# ACDC_Flyback.net
KiCad netlist of a schematic drawn in Altium Designer
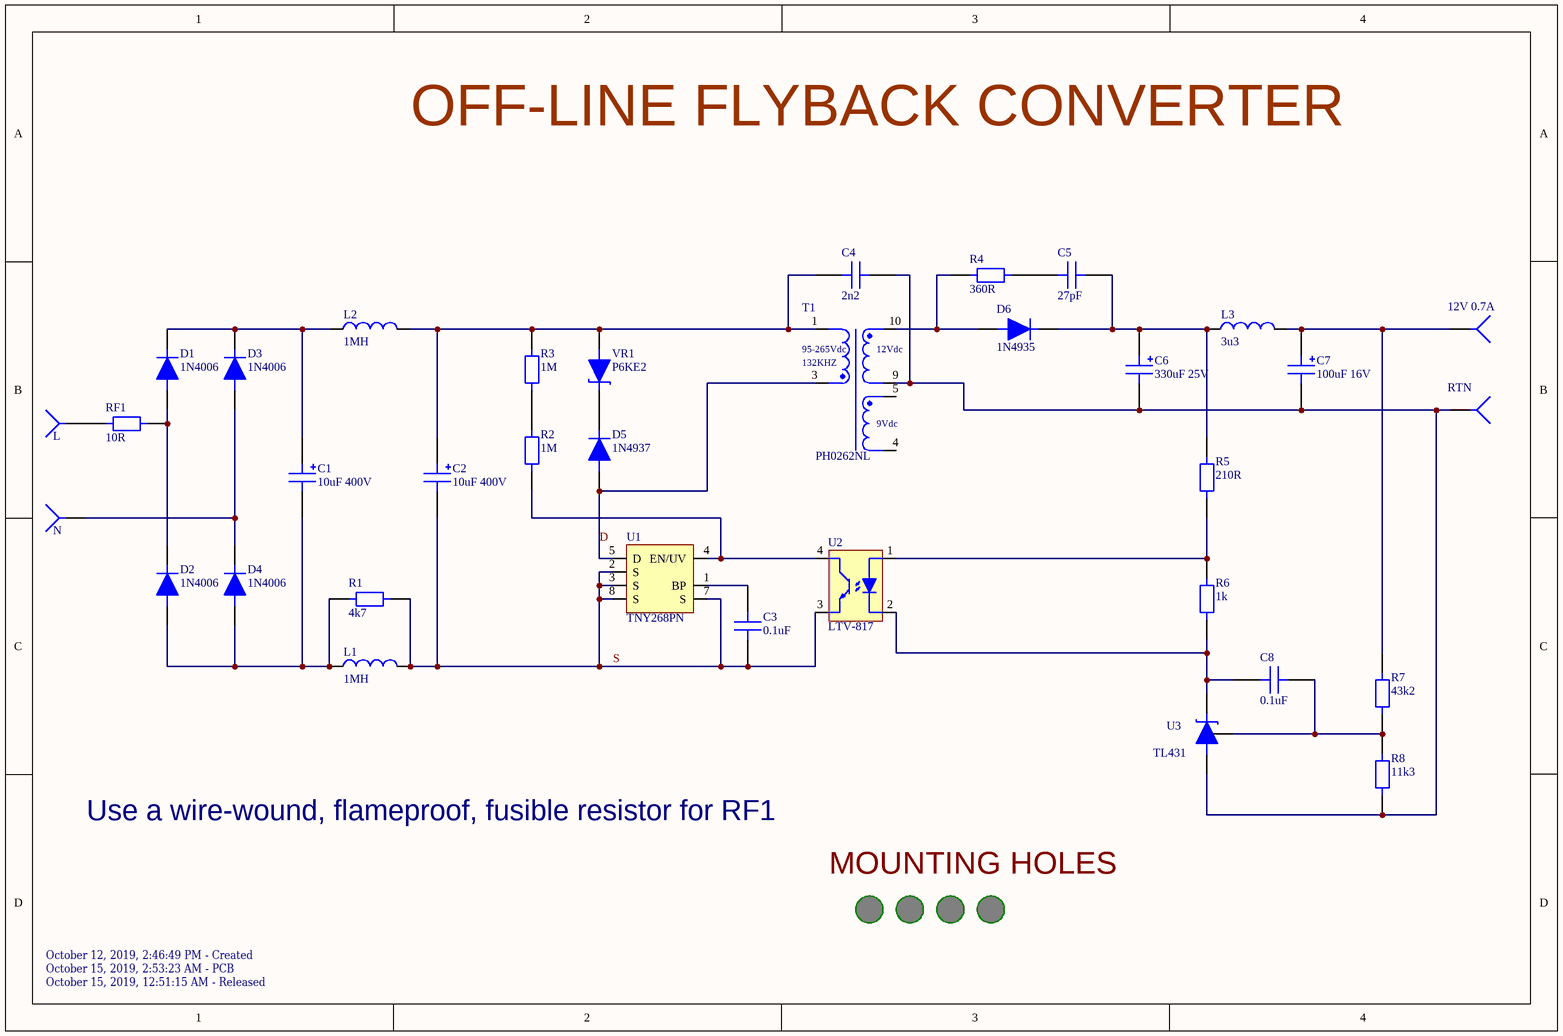
[diagram p0: ACDC_Flyback.SchDoc]

(export (version "E")
  (design (tool "Eeschema 10.0.6"))
  (components
    (comp (ref "1")
      (value "MNT HOLE 3.5mm")
      (footprint "MNT HOLE 3.5mm")
      (libsource (lib "Pwrlib") (part "MNT HOLE 3.5mm"))
    )
    (comp (ref "2")
      (value "MNT HOLE 3.5mm")
      (footprint "MNT HOLE 3.5mm")
      (libsource (lib "Pwrlib") (part "MNT HOLE 3.5mm"))
    )
    (comp (ref "3")
      (value "MNT HOLE 3.5mm")
      (footprint "MNT HOLE 3.5mm")
      (libsource (lib "Pwrlib") (part "MNT HOLE 3.5mm"))
    )
    (comp (ref "4")
      (value "MNT HOLE 3.5mm")
      (footprint "MNT HOLE 3.5mm")
      (libsource (lib "Pwrlib") (part "MNT HOLE 3.5mm"))
    )
    (comp (ref "C1")
      (value "10uF 400V")
      (footprint "CAP 10x20")
      (description "CAP ALUM 10uF 400V 10x20")
      (fields
        (field (name "MANUFACTURER") "United Chemi-Con")
        (field (name "MANUFACTURER PART NUMBER") "EKXG401ETD100MJ20S")
      )
      (libsource (lib "Pwrlib") (part "EKXG401ETD100MJ20S"))
    )
    (comp (ref "C2")
      (value "10uF 400V")
      (footprint "CAP 10x20")
      (description "CAP ALUM 10uF 400V 10x20")
      (fields
        (field (name "MANUFACTURER") "United Chemi-Con")
        (field (name "MANUFACTURER PART NUMBER") "EKXG401ETD100MJ20S")
      )
      (libsource (lib "Pwrlib") (part "EKXG401ETD100MJ20S"))
    )
    (comp (ref "C3")
      (value "0.1uF")
      (footprint "CAP CER 5mm")
      (description "CAP CER 0.1UF 50V X7R RADIAL")
      (fields
        (field (name "MANUFACTURER") "Vishay BCcomponents")
        (field (name "MANUFACTURER PART NUMBER") "K104K15X7RF5TL2")
      )
      (libsource (lib "Pwrlib") (part "K104K15X7RF5TL2"))
    )
    (comp (ref "C4")
      (value "2n2")
      (footprint "CAP X1/Y1 9.5mm")
      (description "CAP CER 2u2 X1/Y1 400VAC/500VAC Y5U 20% (10.9 X 5.7mm) Radial 9.5mm Bulk")
      (fields (field (name "MANUFACTURER") "Vishay") (field (name "MANUFACTURER PART NUMBER") "440LD22-R"))
      (libsource (lib "Pwrlib") (part "440LD22-R"))
    )
    (comp (ref "C5")
      (value "27pF")
      (footprint "CAP CER 5mm")
      (description "CAP CER 27pF 100V C0G/NP0 RADIAL")
      (fields
        (field (name "MANUFACTURER") "Murata")
        (field (name "MANUFACTURER PART NUMBER") "RCE5C2A270J0M1H03A")
      )
      (libsource (lib "Pwrlib") (part "RCE5C2A270J0M1H03A"))
    )
    (comp (ref "C6")
      (value "330uF 25V")
      (footprint "CAP 8x16")
      (description "CAP ALUM 330uF 25V 20% 105C Radial 8x16 Aluminum Electrolytic Capacitors")
      (fields
        (field (name "MANUFACTURER") "KEMET")
        (field (name "MANUFACTURER PART NUMBER") "ESY337M025AG8AA")
      )
      (libsource (lib "Pwrlib") (part "ESY337M025AG8AA"))
    )
    (comp (ref "C7")
      (value "100uF 16V")
      (footprint "CAP 5x11")
      (description "CAP ALUM 100UF 16V 20% THRU HOLE")
      (fields
        (field (name "MANUFACTURER") "KEMET")
        (field (name "MANUFACTURER PART NUMBER") "ESL107M016AC3AA")
      )
      (libsource (lib "Pwrlib") (part "ESL107M016AC3AA"))
    )
    (comp (ref "C8")
      (value "0.1uF")
      (footprint "CAP CER 5mm")
      (description "CAP CER 0.1UF 50V X7R RADIAL")
      (fields
        (field (name "MANUFACTURER") "Vishay BCcomponents")
        (field (name "MANUFACTURER PART NUMBER") "K104K15X7RF5TL2")
      )
      (libsource (lib "Pwrlib") (part "K104K15X7RF5TL2"))
    )
    (comp (ref "D1")
      (value "1N4006")
      (footprint "Diode H 8.5mm")
      (description "DIODE 1N4006 GEN PURP 800V 1A DO204AL")
      (fields
        (field (name "MANUFACTURER") "Vishay Intertechnology")
        (field (name "MANUFACTURER PART NUMBER") "1N4006E354")
      )
      (libsource (lib "Pwrlib") (part "1N4006E354"))
    )
    (comp (ref "D2")
      (value "1N4006")
      (footprint "Diode H 8.5mm")
      (description "DIODE 1N4006 GEN PURP 800V 1A DO204AL")
      (fields
        (field (name "MANUFACTURER") "Vishay Intertechnology")
        (field (name "MANUFACTURER PART NUMBER") "1N4006E354")
      )
      (libsource (lib "Pwrlib") (part "1N4006E354"))
    )
    (comp (ref "D3")
      (value "1N4006")
      (footprint "Diode H 8.5mm")
      (description "DIODE 1N4006 GEN PURP 800V 1A DO204AL")
      (fields
        (field (name "MANUFACTURER") "Vishay Intertechnology")
        (field (name "MANUFACTURER PART NUMBER") "1N4006E354")
      )
      (libsource (lib "Pwrlib") (part "1N4006E354"))
    )
    (comp (ref "D4")
      (value "1N4006")
      (footprint "Diode H 8.5mm")
      (description "DIODE 1N4006 GEN PURP 800V 1A DO204AL")
      (fields
        (field (name "MANUFACTURER") "Vishay Intertechnology")
        (field (name "MANUFACTURER PART NUMBER") "1N4006E354")
      )
      (libsource (lib "Pwrlib") (part "1N4006E354"))
    )
    (comp (ref "D5")
      (value "1N4937")
      (footprint "Diode H 8.5mm")
      (description "DIODE 1N4937 Rectifiers 1.0 Amp 600 Volt Glass Passivated")
      (fields
        (field (name "MANUFACTURER") "Vishay Semiconductors")
        (field (name "MANUFACTURER PART NUMBER") "1N4937GP-E3/73")
      )
      (libsource (lib "Pwrlib") (part "1N4937GP-E3/73"))
    )
    (comp (ref "D6")
      (value "1N4935")
      (footprint "Diode H 8.5mm")
      (description "DIODE 1N4935 Rectifiers 1.0 Amp 200 Volt")
      (fields
        (field (name "MANUFACTURER") "Vishay Semiconductors")
        (field (name "MANUFACTURER PART NUMBER") "1N4935-E3/54")
      )
      (libsource (lib "Pwrlib") (part "1N4935-E3/54"))
    )
    (comp (ref "L1")
      (value "1MH")
      (footprint "IND 4mm BLUE")
      (description "IND 1MH 180MA 4 OHM TH")
      (fields (field (name "MANUFACTURER") "KEMET") (field (name "MANUFACTURER PART NUMBER") "SBC2-102-181"))
      (libsource (lib "Pwrlib") (part "SBC2-102-181"))
    )
    (comp (ref "L2")
      (value "1MH")
      (footprint "IND 4mm BLUE")
      (description "IND 1MH 180MA 4 OHM TH")
      (fields (field (name "MANUFACTURER") "KEMET") (field (name "MANUFACTURER PART NUMBER") "SBC2-102-181"))
      (libsource (lib "Pwrlib") (part "SBC2-102-181"))
    )
    (comp (ref "L3")
      (value "3u3")
      (footprint "IND 4mm BLACK")
      (description "IND 3u3 5.5A 25 MOHM TH")
      (fields
        (field (name "MANUFACTURER") "Bourns")
        (field (name "MANUFACTURER PART NUMBER") "RL622-3R3K-RC")
      )
      (libsource (lib "Pwrlib") (part "RL622-3R3K-RC"))
    )
    (comp (ref "R1")
      (value "4k7")
      (footprint "RES V 0.25W 5mm")
      (description "RES T/H 4k7 OHM 1/4W 5% AXIAL")
      (fields
        (field (name "MANUFACTURER") "Yageo")
        (field (name "MANUFACTURER PART NUMBER") "CFR-25JB-52-4K7")
      )
      (libsource (lib "Pwrlib") (part "CFR-25JB-52-4K7"))
    )
    (comp (ref "R2")
      (value "1M")
      (footprint "RES H 0.25W 8.5mm")
      (description "RES T/H 1M OHM 1/4W 5% AXIAL")
      (fields
        (field (name "MANUFACTURER") "Yageo")
        (field (name "MANUFACTURER PART NUMBER") "CFR-25JB-52-1M")
      )
      (libsource (lib "Pwrlib") (part "CFR-25JB-52-1M"))
    )
    (comp (ref "R3")
      (value "1M")
      (footprint "RES H 0.25W 8.5mm")
      (description "RES T/H 1M OHM 1/4W 5% AXIAL")
      (fields
        (field (name "MANUFACTURER") "Yageo")
        (field (name "MANUFACTURER PART NUMBER") "CFR-25JB-52-1M")
      )
      (libsource (lib "Pwrlib") (part "CFR-25JB-52-1M"))
    )
    (comp (ref "R4")
      (value "360R")
      (footprint "RES V 0.25W 5mm")
      (description "RES T/H 360 OHM 1/4W 5% AXIAL")
      (fields
        (field (name "MANUFACTURER") "Yageo")
        (field (name "MANUFACTURER PART NUMBER") "CFR-25JB-52-360R")
      )
      (libsource (lib "Pwrlib") (part "CFR-25JB-52-360R"))
    )
    (comp (ref "R5")
      (value "210R")
      (footprint "RES V 0.25W 5mm")
      (description "RES T/H 210 OHM 1/4W 1%")
      (fields
        (field (name "MANUFACTURER") "Yageo")
        (field (name "MANUFACTURER PART NUMBER") "MFR-25FBF52-210R")
      )
      (libsource (lib "Pwrlib") (part "MFR-25FBF52-210R"))
    )
    (comp (ref "R6")
      (value "1k")
      (footprint "RES V 0.25W 5mm")
      (description "RES T/H 1K OHM 1/4W 1%")
      (fields
        (field (name "MANUFACTURER") "Yageo")
        (field (name "MANUFACTURER PART NUMBER") "MFR-25FBF52-1K")
      )
      (libsource (lib "Pwrlib") (part "MFR-25FBF52-1K"))
    )
    (comp (ref "R7")
      (value "43k2")
      (footprint "RES V 0.25W 5mm")
      (description "RES T/H 43k2 OHM 1/4W 1%")
      (fields
        (field (name "MANUFACTURER") "Yageo")
        (field (name "MANUFACTURER PART NUMBER") "MFR-25FBF52-43K2")
      )
      (libsource (lib "Pwrlib") (part "MFR-25FBF52-43K2"))
    )
    (comp (ref "R8")
      (value "11k3")
      (footprint "RES V 0.25W 5mm")
      (description "RES T/H 11k3 OHM 1/4W 1% Metal Film")
      (fields
        (field (name "MANUFACTURER") "Yageo")
        (field (name "MANUFACTURER PART NUMBER") "MFR-25FBF52-11K3")
      )
      (libsource (lib "Pwrlib") (part "MFR-25FBF52-11K3"))
    )
    (comp (ref "RF1")
      (value "10R")
      (footprint "RES V 2W 5mm")
      (description "RES T/H 10 OHM 2W Wirewound 5% ±200ppm/C Conformal AXL Ammo Pack")
      (fields (field (name "MANUFACTURER") "Bourns") (field (name "MANUFACTURER PART NUMBER") "FW20A10R0JA"))
      (libsource (lib "Pwrlib") (part "FW20A10R0JA"))
    )
    (comp (ref "T1")
      (value "PH0262NL")
      (footprint "PH0262NL")
      (description "Transformer 3000Vrms 95V/265V Prim. 12V/9V Sec. Through Hole")
      (fields (field (name "MANUFACTURER") "Pulse"))
      (libsource (lib "Pwrlib") (part "PH0262NL"))
    )
    (comp (ref "U1")
      (value "TNY268PN")
      (footprint "DIP8")
      (description "IC TNY268PN OFF LINE SWITCHER, DIP8, 268")
      (fields (field (name "MANUFACTURER") "Power Integrations"))
      (libsource (lib "Pwrlib") (part "TNY268PN"))
    )
    (comp (ref "U2")
      (value "LTV-817")
      (footprint "LTV-8x7")
      (description "OPT DC-IN 1-CH Transistor DC-OUT 4-Pin PDIP")
      (fields
        (field (name "MANUFACTURER") "Vishay Lite-On")
        (field (name "MANUFACTURER PART NUMBER") "LTV-817-A")
      )
      (libsource (lib "Pwrlib") (part "LTV-817-A"))
    )
    (comp (ref "U3")
      (value "TL431")
      (footprint "TO-92 (TO-226)")
      (description "IC TL431 VREF SHUNT ADJ TO92-3")
      (fields
        (field (name "MANUFACTURER") "ON Semiconductor")
        (field (name "MANUFACTURER PART NUMBER") "TL431ACLPRAG")
      )
      (libsource (lib "Pwrlib") (part "TL431ACLPRAG"))
    )
    (comp (ref "VR1")
      (value "P6KE2")
      (footprint "Diode H 8.5mm")
      (description "DIODE TVS 171VWM 274VC DO204AC")
      (fields
        (field (name "MANUFACTURER") "Vishay Semiconductors")
        (field (name "MANUFACTURER PART NUMBER") "P6KE200A-E3/54")
      )
      (libsource (lib "Pwrlib") (part "P6KE200A-E3/54"))
    )
    (comp (ref "X1")
      (value "L")
      (footprint "Power Terminal")
      (libsource (lib "Pwrlib") (part "Power Terminal"))
    )
    (comp (ref "X2")
      (value "N")
      (footprint "Power Terminal")
      (libsource (lib "Pwrlib") (part "Power Terminal"))
    )
    (comp (ref "X3")
      (value "12V 0.7A")
      (footprint "Power Terminal")
      (libsource (lib "Pwrlib") (part "Power Terminal"))
    )
    (comp (ref "X4")
      (value "RTN")
      (footprint "Power Terminal")
      (libsource (lib "Pwrlib") (part "Power Terminal"))
    )
  )
  (nets
    (net (code "1") (name "/D") (class "Default")
      (node (ref "D5") (pin "1") (pinfunction "1_1") (pintype "passive"))
      (node (ref "T1") (pin "3") (pinfunction "3_3") (pintype "passive"))
      (node (ref "U1") (pin "5") (pinfunction "D_5") (pintype "passive"))
    )
    (net (code "2") (name "/S") (class "Default")
      (node (ref "C2") (pin "1") (pinfunction "1_1") (pintype "passive"))
      (node (ref "C3") (pin "1") (pinfunction "1_1") (pintype "passive"))
      (node (ref "L1") (pin "2") (pinfunction "2_2") (pintype "passive"))
      (node (ref "R1") (pin "2") (pinfunction "2_2") (pintype "passive"))
      (node (ref "U1") (pin "2") (pinfunction "S_2") (pintype "passive"))
      (node (ref "U1") (pin "3") (pinfunction "S_3") (pintype "passive"))
      (node (ref "U1") (pin "7") (pinfunction "S_7") (pintype "passive"))
      (node (ref "U1") (pin "8") (pinfunction "S_8") (pintype "passive"))
      (node (ref "U2") (pin "3") (pinfunction "3_3") (pintype "passive"))
    )
    (net (code "3") (name "Net-(C1-Pad1)") (class "Default")
      (node (ref "C1") (pin "1") (pinfunction "1_1") (pintype "passive"))
      (node (ref "D2") (pin "1") (pinfunction "1_1") (pintype "passive"))
      (node (ref "D4") (pin "1") (pinfunction "1_1") (pintype "passive"))
      (node (ref "L1") (pin "1") (pinfunction "1_1") (pintype "passive"))
      (node (ref "R1") (pin "1") (pinfunction "1_1") (pintype "passive"))
    )
    (net (code "4") (name "Net-(C1-Pad2)") (class "Default")
      (node (ref "C1") (pin "2") (pinfunction "2_2") (pintype "passive"))
      (node (ref "D1") (pin "2") (pinfunction "2_2") (pintype "passive"))
      (node (ref "D3") (pin "2") (pinfunction "2_2") (pintype "passive"))
      (node (ref "L2") (pin "1") (pinfunction "1_1") (pintype "passive"))
    )
    (net (code "5") (name "Net-(C2-Pad2)") (class "Default")
      (node (ref "C2") (pin "2") (pinfunction "2_2") (pintype "passive"))
      (node (ref "C4") (pin "1") (pinfunction "1_1") (pintype "passive"))
      (node (ref "L2") (pin "2") (pinfunction "2_2") (pintype "passive"))
      (node (ref "R3") (pin "2") (pinfunction "2_2") (pintype "passive"))
      (node (ref "T1") (pin "1") (pinfunction "1_1") (pintype "passive"))
      (node (ref "VR1") (pin "1") (pinfunction "1_1") (pintype "passive"))
    )
    (net (code "6") (name "Net-(C4-Pad2)") (class "Default")
      (node (ref "C4") (pin "2") (pinfunction "2_2") (pintype "passive"))
      (node (ref "C6") (pin "1") (pinfunction "1_1") (pintype "passive"))
      (node (ref "C7") (pin "1") (pinfunction "1_1") (pintype "passive"))
      (node (ref "R8") (pin "1") (pinfunction "1_1") (pintype "passive"))
      (node (ref "T1") (pin "9") (pinfunction "9_9") (pintype "passive"))
      (node (ref "U3") (pin "2") (pinfunction "2_2") (pintype "passive"))
      (node (ref "X4") (pin "1") (pinfunction "1_1") (pintype "passive"))
    )
    (net (code "7") (name "Net-(C5-Pad1)") (class "Default")
      (node (ref "C5") (pin "1") (pinfunction "1_1") (pintype "passive"))
      (node (ref "R4") (pin "2") (pinfunction "2_2") (pintype "passive"))
    )
    (net (code "8") (name "Net-(C5-Pad2)") (class "Default")
      (node (ref "C5") (pin "2") (pinfunction "2_2") (pintype "passive"))
      (node (ref "C6") (pin "2") (pinfunction "2_2") (pintype "passive"))
      (node (ref "D6") (pin "2") (pinfunction "2_2") (pintype "passive"))
      (node (ref "L3") (pin "1") (pinfunction "1_1") (pintype "passive"))
      (node (ref "R5") (pin "1") (pinfunction "1_1") (pintype "passive"))
    )
    (net (code "9") (name "Net-(C7-Pad2)") (class "Default")
      (node (ref "C7") (pin "2") (pinfunction "2_2") (pintype "passive"))
      (node (ref "L3") (pin "2") (pinfunction "2_2") (pintype "passive"))
      (node (ref "R7") (pin "2") (pinfunction "2_2") (pintype "passive"))
      (node (ref "X3") (pin "1") (pinfunction "1_1") (pintype "passive"))
    )
    (net (code "10") (name "Net-(C8-Pad1)") (class "Default")
      (node (ref "C8") (pin "1") (pinfunction "1_1") (pintype "passive"))
      (node (ref "R6") (pin "1") (pinfunction "1_1") (pintype "passive"))
      (node (ref "U2") (pin "2") (pinfunction "2_2") (pintype "passive"))
      (node (ref "U3") (pin "3") (pinfunction "3_3") (pintype "passive"))
    )
    (net (code "11") (name "Net-(C8-Pad2)") (class "Default")
      (node (ref "C8") (pin "2") (pinfunction "2_2") (pintype "passive"))
      (node (ref "R7") (pin "1") (pinfunction "1_1") (pintype "passive"))
      (node (ref "R8") (pin "2") (pinfunction "2_2") (pintype "passive"))
      (node (ref "U3") (pin "1") (pinfunction "1_1") (pintype "passive"))
    )
    (net (code "12") (name "Net-(D1-Pad1)") (class "Default")
      (node (ref "D1") (pin "1") (pinfunction "1_1") (pintype "passive"))
      (node (ref "D2") (pin "2") (pinfunction "2_2") (pintype "passive"))
      (node (ref "RF1") (pin "2") (pinfunction "2_2") (pintype "passive"))
    )
    (net (code "13") (name "Net-(D3-Pad1)") (class "Default")
      (node (ref "D3") (pin "1") (pinfunction "1_1") (pintype "passive"))
      (node (ref "D4") (pin "2") (pinfunction "2_2") (pintype "passive"))
      (node (ref "X2") (pin "1") (pinfunction "1_1") (pintype "passive"))
    )
    (net (code "14") (name "Net-(D5-Pad2)") (class "Default")
      (node (ref "D5") (pin "2") (pinfunction "2_2") (pintype "passive"))
      (node (ref "VR1") (pin "2") (pinfunction "2_2") (pintype "passive"))
    )
    (net (code "15") (name "Net-(D6-Pad1)") (class "Default")
      (node (ref "D6") (pin "1") (pinfunction "1_1") (pintype "passive"))
      (node (ref "R4") (pin "1") (pinfunction "1_1") (pintype "passive"))
      (node (ref "T1") (pin "10") (pinfunction "10_10") (pintype "passive"))
    )
    (net (code "16") (name "Net-(R2-Pad2)") (class "Default")
      (node (ref "R2") (pin "2") (pinfunction "2_2") (pintype "passive"))
      (node (ref "R3") (pin "1") (pinfunction "1_1") (pintype "passive"))
    )
    (net (code "17") (name "Net-(R5-Pad2)") (class "Default")
      (node (ref "R5") (pin "2") (pinfunction "2_2") (pintype "passive"))
      (node (ref "R6") (pin "2") (pinfunction "2_2") (pintype "passive"))
      (node (ref "U2") (pin "1") (pinfunction "1_1") (pintype "passive"))
    )
    (net (code "18") (name "Net-(RF1-Pad1)") (class "Default")
      (node (ref "RF1") (pin "1") (pinfunction "1_1") (pintype "passive"))
      (node (ref "X1") (pin "1") (pinfunction "1_1") (pintype "passive"))
    )
    (net (code "19") (name "Net-(U1-BP)") (class "Default")
      (node (ref "C3") (pin "2") (pinfunction "2_2") (pintype "passive"))
      (node (ref "U1") (pin "1") (pinfunction "BP_1") (pintype "passive"))
    )
    (net (code "20") (name "Net-(U1-EN{slash}UV)") (class "Default")
      (node (ref "R2") (pin "1") (pinfunction "1_1") (pintype "passive"))
      (node (ref "U1") (pin "4") (pinfunction "EN/UV_4") (pintype "passive"))
      (node (ref "U2") (pin "4") (pinfunction "4_4") (pintype "passive"))
    )
    (net (code "21") (name "unconnected-(T1-Pad4)") (class "Default")
      (node (ref "T1") (pin "4") (pinfunction "4_4") (pintype "passive"))
    )
    (net (code "22") (name "unconnected-(T1-Pad5)") (class "Default")
      (node (ref "T1") (pin "5") (pinfunction "5_5") (pintype "passive"))
    )
  )
)
